# Skaarhoj_BI8-1x8v1_1.net
KiCad netlist of a schematic drawn in EAGLE
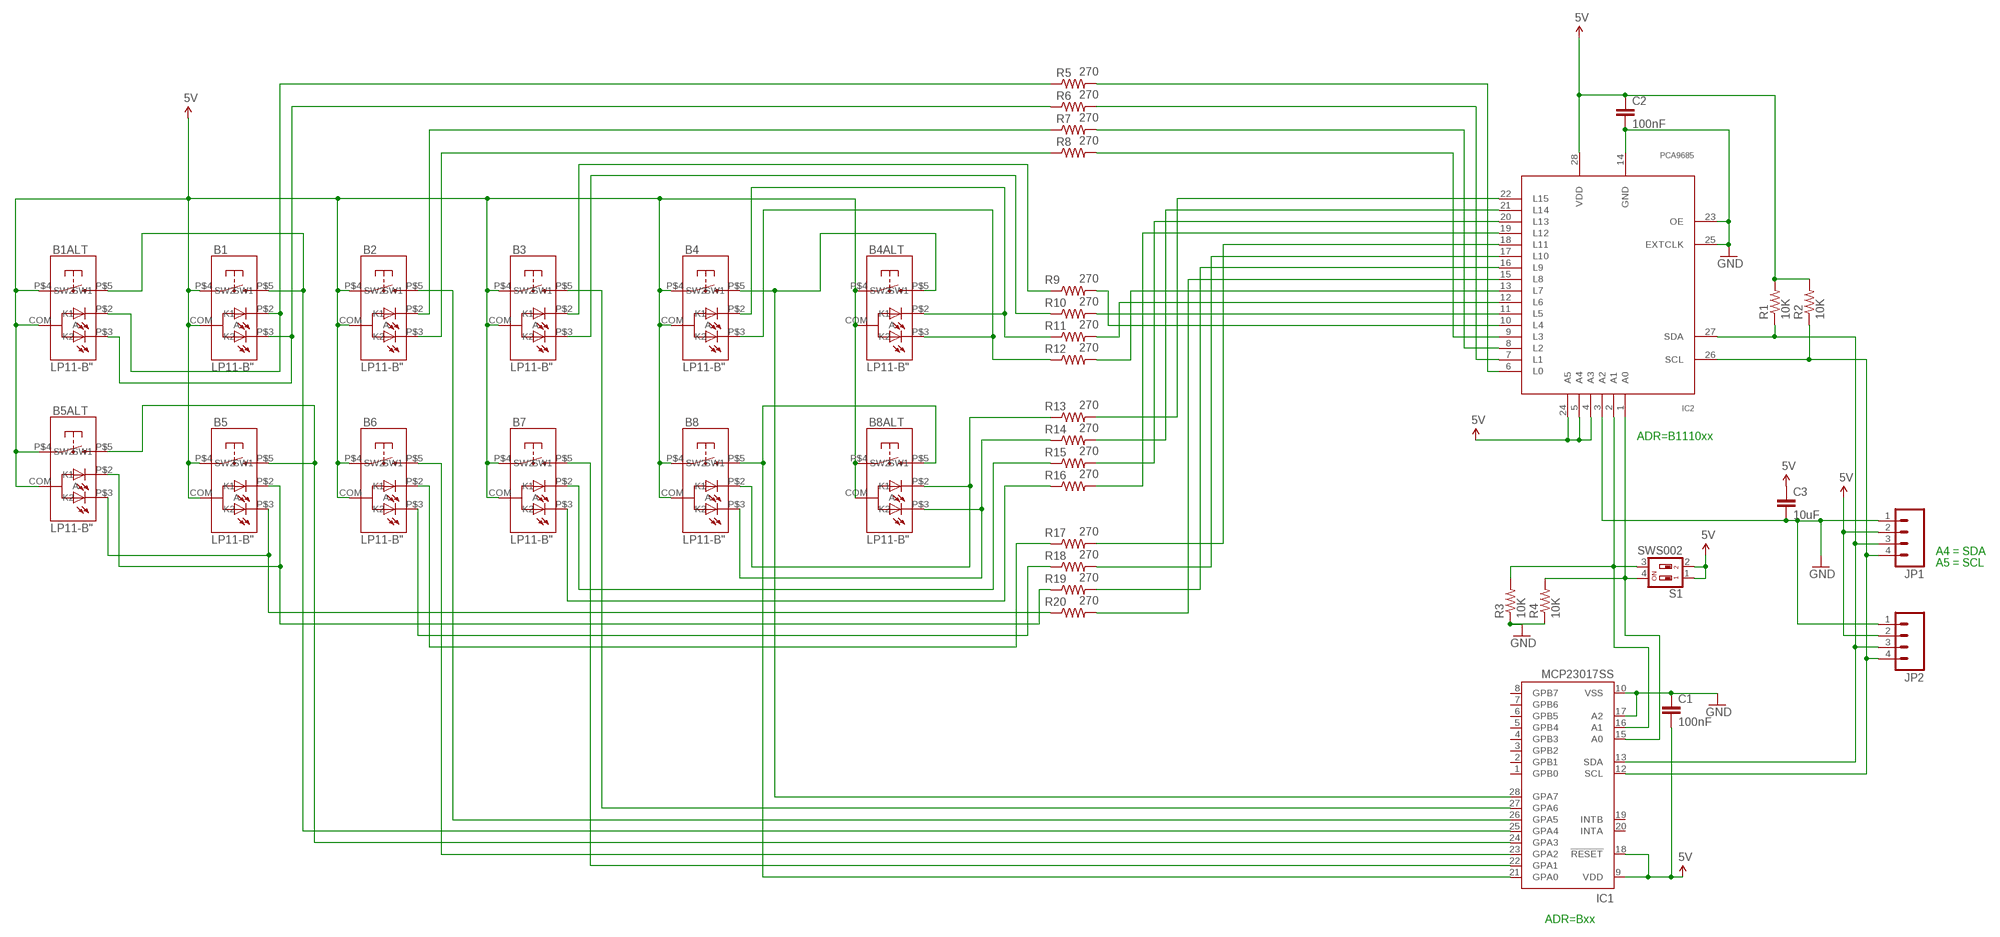
[diagram p0: schematic, sheet 1]

(export (version "E")
  (design (tool "Eeschema 10.0.6"))
  (components
    (comp (ref "B1")
      (value "LP11-B\"")
      (footprint "eagle-import:LP11")
      (libsource (lib "eagle-import") (part "LP11-B{dblquote}"))
    )
    (comp (ref "B1ALT")
      (value "LP11-B\"")
      (footprint "eagle-import:LP11")
      (libsource (lib "eagle-import") (part "LP11-B{dblquote}"))
    )
    (comp (ref "B2")
      (value "LP11-B\"")
      (footprint "eagle-import:LP11")
      (libsource (lib "eagle-import") (part "LP11-B{dblquote}"))
    )
    (comp (ref "B3")
      (value "LP11-B\"")
      (footprint "eagle-import:LP11")
      (libsource (lib "eagle-import") (part "LP11-B{dblquote}"))
    )
    (comp (ref "B4")
      (value "LP11-B\"")
      (footprint "eagle-import:LP11")
      (libsource (lib "eagle-import") (part "LP11-B{dblquote}"))
    )
    (comp (ref "B4ALT")
      (value "LP11-B\"")
      (footprint "eagle-import:LP11")
      (libsource (lib "eagle-import") (part "LP11-B{dblquote}"))
    )
    (comp (ref "B5")
      (value "LP11-B\"")
      (footprint "eagle-import:LP11")
      (libsource (lib "eagle-import") (part "LP11-B{dblquote}"))
    )
    (comp (ref "B5ALT")
      (value "LP11-B\"")
      (footprint "eagle-import:LP11")
      (libsource (lib "eagle-import") (part "LP11-B{dblquote}"))
    )
    (comp (ref "B6")
      (value "LP11-B\"")
      (footprint "eagle-import:LP11")
      (libsource (lib "eagle-import") (part "LP11-B{dblquote}"))
    )
    (comp (ref "B7")
      (value "LP11-B\"")
      (footprint "eagle-import:LP11")
      (libsource (lib "eagle-import") (part "LP11-B{dblquote}"))
    )
    (comp (ref "B8")
      (value "LP11-B\"")
      (footprint "eagle-import:LP11")
      (libsource (lib "eagle-import") (part "LP11-B{dblquote}"))
    )
    (comp (ref "B8ALT")
      (value "LP11-B\"")
      (footprint "eagle-import:LP11")
      (libsource (lib "eagle-import") (part "LP11-B{dblquote}"))
    )
    (comp (ref "C1")
      (value "100nF")
      (footprint "eagle-import:0603-CAP")
      (libsource (lib "eagle-import") (part "CAP0603-CAP"))
    )
    (comp (ref "C2")
      (value "100nF")
      (footprint "eagle-import:0603-CAP")
      (libsource (lib "eagle-import") (part "CAP0603-CAP"))
    )
    (comp (ref "C3")
      (value "10uF")
      (footprint "eagle-import:0805")
      (libsource (lib "eagle-import") (part "CAP0805"))
    )
    (comp (ref "IC1")
      (value "MCP23017SS")
      (footprint "eagle-import:SSOP28")
      (fields
        (field (name "MF") "MICROCHIP")
        (field (name "MPN") "MCP23017-E/SS")
        (field (name "MPN_1") "MCP23017-E/SS")
        (field (name "OC_FARNELL") "1467674")
        (field (name "OC_NEWARK") "31K2960")
      )
      (libsource (lib "eagle-import") (part "MCP23017SS"))
    )
    (comp (ref "IC2")
      (value "PCA9685")
      (footprint "eagle-import:TSSOP28")
      (libsource (lib "eagle-import") (part "PCA9685"))
    )
    (comp (ref "JP1")
      (value "M04PTH")
      (footprint "eagle-import:1X04")
      (libsource (lib "eagle-import") (part "M04PTH"))
    )
    (comp (ref "JP2")
      (value "M04PTH")
      (footprint "eagle-import:1X04")
      (libsource (lib "eagle-import") (part "M04PTH"))
    )
    (comp (ref "R1")
      (value "10K")
      (footprint "eagle-import:0603-RES")
      (libsource (lib "eagle-import") (part "RESISTOR0603-RES"))
    )
    (comp (ref "R2")
      (value "10K")
      (footprint "eagle-import:0603-RES")
      (libsource (lib "eagle-import") (part "RESISTOR0603-RES"))
    )
    (comp (ref "R3")
      (value "10K")
      (footprint "eagle-import:0603-RES")
      (libsource (lib "eagle-import") (part "RESISTOR0603-RES"))
    )
    (comp (ref "R4")
      (value "10K")
      (footprint "eagle-import:0603-RES")
      (libsource (lib "eagle-import") (part "RESISTOR0603-RES"))
    )
    (comp (ref "R5")
      (value "270")
      (footprint "eagle-import:0603-RES")
      (libsource (lib "eagle-import") (part "RESISTOR0603-RES"))
    )
    (comp (ref "R6")
      (value "270")
      (footprint "eagle-import:0603-RES")
      (libsource (lib "eagle-import") (part "RESISTOR0603-RES"))
    )
    (comp (ref "R7")
      (value "270")
      (footprint "eagle-import:0603-RES")
      (libsource (lib "eagle-import") (part "RESISTOR0603-RES"))
    )
    (comp (ref "R8")
      (value "270")
      (footprint "eagle-import:0603-RES")
      (libsource (lib "eagle-import") (part "RESISTOR0603-RES"))
    )
    (comp (ref "R9")
      (value "270")
      (footprint "eagle-import:0603-RES")
      (libsource (lib "eagle-import") (part "RESISTOR0603-RES"))
    )
    (comp (ref "R10")
      (value "270")
      (footprint "eagle-import:0603-RES")
      (libsource (lib "eagle-import") (part "RESISTOR0603-RES"))
    )
    (comp (ref "R11")
      (value "270")
      (footprint "eagle-import:0603-RES")
      (libsource (lib "eagle-import") (part "RESISTOR0603-RES"))
    )
    (comp (ref "R12")
      (value "270")
      (footprint "eagle-import:0603-RES")
      (libsource (lib "eagle-import") (part "RESISTOR0603-RES"))
    )
    (comp (ref "R13")
      (value "270")
      (footprint "eagle-import:0603-RES")
      (libsource (lib "eagle-import") (part "RESISTOR0603-RES"))
    )
    (comp (ref "R14")
      (value "270")
      (footprint "eagle-import:0603-RES")
      (libsource (lib "eagle-import") (part "RESISTOR0603-RES"))
    )
    (comp (ref "R15")
      (value "270")
      (footprint "eagle-import:0603-RES")
      (libsource (lib "eagle-import") (part "RESISTOR0603-RES"))
    )
    (comp (ref "R16")
      (value "270")
      (footprint "eagle-import:0603-RES")
      (libsource (lib "eagle-import") (part "RESISTOR0603-RES"))
    )
    (comp (ref "R17")
      (value "270")
      (footprint "eagle-import:0603-RES")
      (libsource (lib "eagle-import") (part "RESISTOR0603-RES"))
    )
    (comp (ref "R18")
      (value "270")
      (footprint "eagle-import:0603-RES")
      (libsource (lib "eagle-import") (part "RESISTOR0603-RES"))
    )
    (comp (ref "R19")
      (value "270")
      (footprint "eagle-import:0603-RES")
      (libsource (lib "eagle-import") (part "RESISTOR0603-RES"))
    )
    (comp (ref "R20")
      (value "270")
      (footprint "eagle-import:0603-RES")
      (libsource (lib "eagle-import") (part "RESISTOR0603-RES"))
    )
    (comp (ref "S1")
      (value "SWS002")
      (footprint "eagle-import:SMS-002")
      (libsource (lib "eagle-import") (part "SWS002"))
    )
  )
  (nets
    (net (code "1") (name "5V") (class "Default")
      (node (ref "B1") (pin "COM") (pinfunction "A_COM") (pintype "bidirectional"))
      (node (ref "B1") (pin "P$4") (pinfunction "SW1_P$4") (pintype "bidirectional"))
      (node (ref "B1ALT") (pin "COM") (pinfunction "A_COM") (pintype "bidirectional"))
      (node (ref "B1ALT") (pin "P$4") (pinfunction "SW1_P$4") (pintype "bidirectional"))
      (node (ref "B2") (pin "COM") (pinfunction "A_COM") (pintype "bidirectional"))
      (node (ref "B2") (pin "P$4") (pinfunction "SW1_P$4") (pintype "bidirectional"))
      (node (ref "B3") (pin "COM") (pinfunction "A_COM") (pintype "bidirectional"))
      (node (ref "B3") (pin "P$4") (pinfunction "SW1_P$4") (pintype "bidirectional"))
      (node (ref "B4") (pin "COM") (pinfunction "A_COM") (pintype "bidirectional"))
      (node (ref "B4") (pin "P$4") (pinfunction "SW1_P$4") (pintype "bidirectional"))
      (node (ref "B4ALT") (pin "COM") (pinfunction "A_COM") (pintype "bidirectional"))
      (node (ref "B4ALT") (pin "P$4") (pinfunction "SW1_P$4") (pintype "bidirectional"))
      (node (ref "B5") (pin "COM") (pinfunction "A_COM") (pintype "bidirectional"))
      (node (ref "B5") (pin "P$4") (pinfunction "SW1_P$4") (pintype "bidirectional"))
      (node (ref "B5ALT") (pin "COM") (pinfunction "A_COM") (pintype "bidirectional"))
      (node (ref "B5ALT") (pin "P$4") (pinfunction "SW1_P$4") (pintype "bidirectional"))
      (node (ref "B6") (pin "COM") (pinfunction "A_COM") (pintype "bidirectional"))
      (node (ref "B6") (pin "P$4") (pinfunction "SW1_P$4") (pintype "bidirectional"))
      (node (ref "B7") (pin "COM") (pinfunction "A_COM") (pintype "bidirectional"))
      (node (ref "B7") (pin "P$4") (pinfunction "SW1_P$4") (pintype "bidirectional"))
      (node (ref "B8") (pin "COM") (pinfunction "A_COM") (pintype "bidirectional"))
      (node (ref "B8") (pin "P$4") (pinfunction "SW1_P$4") (pintype "bidirectional"))
      (node (ref "B8ALT") (pin "COM") (pinfunction "A_COM") (pintype "bidirectional"))
      (node (ref "B8ALT") (pin "P$4") (pinfunction "SW1_P$4") (pintype "bidirectional"))
      (node (ref "C1") (pin "2") (pinfunction "2_2") (pintype "passive"))
      (node (ref "C2") (pin "1") (pinfunction "1_1") (pintype "passive"))
      (node (ref "C3") (pin "1") (pinfunction "1_1") (pintype "passive"))
      (node (ref "IC1") (pin "18") (pinfunction "~{RESET}_18") (pintype "input"))
      (node (ref "IC1") (pin "9") (pinfunction "VDD_9") (pintype "power_in"))
      (node (ref "IC2") (pin "24") (pinfunction "A5_24") (pintype "input"))
      (node (ref "IC2") (pin "28") (pinfunction "VDD_28") (pintype "power_in"))
      (node (ref "IC2") (pin "4") (pinfunction "A3_4") (pintype "input"))
      (node (ref "IC2") (pin "5") (pinfunction "A4_5") (pintype "input"))
      (node (ref "JP1") (pin "2") (pinfunction "2_2") (pintype "passive"))
      (node (ref "JP2") (pin "2") (pinfunction "2_2") (pintype "passive"))
      (node (ref "R1") (pin "2") (pinfunction "2_2") (pintype "passive"))
      (node (ref "R2") (pin "2") (pinfunction "2_2") (pintype "passive"))
      (node (ref "S1") (pin "1") (pinfunction "1_1") (pintype "passive"))
      (node (ref "S1") (pin "2") (pinfunction "2_2") (pintype "passive"))
    )
    (net (code "2") (name "GND") (class "Default")
      (node (ref "C1") (pin "1") (pinfunction "1_1") (pintype "passive"))
      (node (ref "C2") (pin "2") (pinfunction "2_2") (pintype "passive"))
      (node (ref "C3") (pin "2") (pinfunction "2_2") (pintype "passive"))
      (node (ref "IC1") (pin "10") (pinfunction "VSS_10") (pintype "power_in"))
      (node (ref "IC1") (pin "17") (pinfunction "A2_17") (pintype "input"))
      (node (ref "IC2") (pin "14") (pinfunction "GND_14") (pintype "power_in"))
      (node (ref "IC2") (pin "23") (pinfunction "OE_23") (pintype "input"))
      (node (ref "IC2") (pin "25") (pinfunction "EXTCLK_25") (pintype "input"))
      (node (ref "IC2") (pin "3") (pinfunction "A2_3") (pintype "input"))
      (node (ref "JP1") (pin "1") (pinfunction "1_1") (pintype "passive"))
      (node (ref "JP2") (pin "1") (pinfunction "1_1") (pintype "passive"))
      (node (ref "R3") (pin "1") (pinfunction "1_1") (pintype "passive"))
      (node (ref "R4") (pin "1") (pinfunction "1_1") (pintype "passive"))
    )
    (net (code "3") (name "Net-(B1-K1)") (class "Default")
      (node (ref "B1") (pin "P$2") (pinfunction "K1_P$2") (pintype "bidirectional"))
      (node (ref "B1ALT") (pin "P$2") (pinfunction "K1_P$2") (pintype "bidirectional"))
      (node (ref "R5") (pin "1") (pinfunction "1_1") (pintype "passive"))
    )
    (net (code "4") (name "Net-(B1-K2)") (class "Default")
      (node (ref "B1") (pin "P$3") (pinfunction "K2_P$3") (pintype "bidirectional"))
      (node (ref "B1ALT") (pin "P$3") (pinfunction "K2_P$3") (pintype "bidirectional"))
      (node (ref "R6") (pin "1") (pinfunction "1_1") (pintype "passive"))
    )
    (net (code "5") (name "Net-(B1-SW2)") (class "Default")
      (node (ref "B1") (pin "P$5") (pinfunction "SW2_P$5") (pintype "bidirectional"))
      (node (ref "B1ALT") (pin "P$5") (pinfunction "SW2_P$5") (pintype "bidirectional"))
      (node (ref "IC1") (pin "25") (pinfunction "GPA4_25") (pintype "bidirectional"))
    )
    (net (code "6") (name "Net-(B2-K1)") (class "Default")
      (node (ref "B2") (pin "P$2") (pinfunction "K1_P$2") (pintype "bidirectional"))
      (node (ref "R7") (pin "1") (pinfunction "1_1") (pintype "passive"))
    )
    (net (code "7") (name "Net-(B2-K2)") (class "Default")
      (node (ref "B2") (pin "P$3") (pinfunction "K2_P$3") (pintype "bidirectional"))
      (node (ref "R8") (pin "1") (pinfunction "1_1") (pintype "passive"))
    )
    (net (code "8") (name "Net-(B2-SW2)") (class "Default")
      (node (ref "B2") (pin "P$5") (pinfunction "SW2_P$5") (pintype "bidirectional"))
      (node (ref "IC1") (pin "26") (pinfunction "GPA5_26") (pintype "bidirectional"))
    )
    (net (code "9") (name "Net-(B3-K1)") (class "Default")
      (node (ref "B3") (pin "P$2") (pinfunction "K1_P$2") (pintype "bidirectional"))
      (node (ref "R9") (pin "1") (pinfunction "1_1") (pintype "passive"))
    )
    (net (code "10") (name "Net-(B3-K2)") (class "Default")
      (node (ref "B3") (pin "P$3") (pinfunction "K2_P$3") (pintype "bidirectional"))
      (node (ref "R10") (pin "1") (pinfunction "1_1") (pintype "passive"))
    )
    (net (code "11") (name "Net-(B3-SW2)") (class "Default")
      (node (ref "B3") (pin "P$5") (pinfunction "SW2_P$5") (pintype "bidirectional"))
      (node (ref "IC1") (pin "27") (pinfunction "GPA6_27") (pintype "bidirectional"))
    )
    (net (code "12") (name "Net-(B4-K1)") (class "Default")
      (node (ref "B4") (pin "P$2") (pinfunction "K1_P$2") (pintype "bidirectional"))
      (node (ref "B4ALT") (pin "P$2") (pinfunction "K1_P$2") (pintype "bidirectional"))
      (node (ref "R11") (pin "1") (pinfunction "1_1") (pintype "passive"))
    )
    (net (code "13") (name "Net-(B4-K2)") (class "Default")
      (node (ref "B4") (pin "P$3") (pinfunction "K2_P$3") (pintype "bidirectional"))
      (node (ref "B4ALT") (pin "P$3") (pinfunction "K2_P$3") (pintype "bidirectional"))
      (node (ref "R12") (pin "1") (pinfunction "1_1") (pintype "passive"))
    )
    (net (code "14") (name "Net-(B4-SW2)") (class "Default")
      (node (ref "B4") (pin "P$5") (pinfunction "SW2_P$5") (pintype "bidirectional"))
      (node (ref "B4ALT") (pin "P$5") (pinfunction "SW2_P$5") (pintype "bidirectional"))
      (node (ref "IC1") (pin "28") (pinfunction "GPA7_28") (pintype "bidirectional"))
    )
    (net (code "15") (name "Net-(B5-K1)") (class "Default")
      (node (ref "B5") (pin "P$2") (pinfunction "K1_P$2") (pintype "bidirectional"))
      (node (ref "B5ALT") (pin "P$2") (pinfunction "K1_P$2") (pintype "bidirectional"))
      (node (ref "R19") (pin "1") (pinfunction "1_1") (pintype "passive"))
    )
    (net (code "16") (name "Net-(B5-K2)") (class "Default")
      (node (ref "B5") (pin "P$3") (pinfunction "K2_P$3") (pintype "bidirectional"))
      (node (ref "B5ALT") (pin "P$3") (pinfunction "K2_P$3") (pintype "bidirectional"))
      (node (ref "R20") (pin "1") (pinfunction "1_1") (pintype "passive"))
    )
    (net (code "17") (name "Net-(B5-SW2)") (class "Default")
      (node (ref "B5") (pin "P$5") (pinfunction "SW2_P$5") (pintype "bidirectional"))
      (node (ref "B5ALT") (pin "P$5") (pinfunction "SW2_P$5") (pintype "bidirectional"))
      (node (ref "IC1") (pin "24") (pinfunction "GPA3_24") (pintype "bidirectional"))
    )
    (net (code "18") (name "Net-(B6-K1)") (class "Default")
      (node (ref "B6") (pin "P$2") (pinfunction "K1_P$2") (pintype "bidirectional"))
      (node (ref "R17") (pin "1") (pinfunction "1_1") (pintype "passive"))
    )
    (net (code "19") (name "Net-(B6-K2)") (class "Default")
      (node (ref "B6") (pin "P$3") (pinfunction "K2_P$3") (pintype "bidirectional"))
      (node (ref "R18") (pin "1") (pinfunction "1_1") (pintype "passive"))
    )
    (net (code "20") (name "Net-(B6-SW2)") (class "Default")
      (node (ref "B6") (pin "P$5") (pinfunction "SW2_P$5") (pintype "bidirectional"))
      (node (ref "IC1") (pin "23") (pinfunction "GPA2_23") (pintype "bidirectional"))
    )
    (net (code "21") (name "Net-(B7-K1)") (class "Default")
      (node (ref "B7") (pin "P$2") (pinfunction "K1_P$2") (pintype "bidirectional"))
      (node (ref "R15") (pin "1") (pinfunction "1_1") (pintype "passive"))
    )
    (net (code "22") (name "Net-(B7-K2)") (class "Default")
      (node (ref "B7") (pin "P$3") (pinfunction "K2_P$3") (pintype "bidirectional"))
      (node (ref "R16") (pin "1") (pinfunction "1_1") (pintype "passive"))
    )
    (net (code "23") (name "Net-(B7-SW2)") (class "Default")
      (node (ref "B7") (pin "P$5") (pinfunction "SW2_P$5") (pintype "bidirectional"))
      (node (ref "IC1") (pin "22") (pinfunction "GPA1_22") (pintype "bidirectional"))
    )
    (net (code "24") (name "Net-(B8-K1)") (class "Default")
      (node (ref "B8") (pin "P$2") (pinfunction "K1_P$2") (pintype "bidirectional"))
      (node (ref "B8ALT") (pin "P$2") (pinfunction "K1_P$2") (pintype "bidirectional"))
      (node (ref "R13") (pin "1") (pinfunction "1_1") (pintype "passive"))
    )
    (net (code "25") (name "Net-(B8-K2)") (class "Default")
      (node (ref "B8") (pin "P$3") (pinfunction "K2_P$3") (pintype "bidirectional"))
      (node (ref "B8ALT") (pin "P$3") (pinfunction "K2_P$3") (pintype "bidirectional"))
      (node (ref "R14") (pin "1") (pinfunction "1_1") (pintype "passive"))
    )
    (net (code "26") (name "Net-(B8-SW2)") (class "Default")
      (node (ref "B8") (pin "P$5") (pinfunction "SW2_P$5") (pintype "bidirectional"))
      (node (ref "B8ALT") (pin "P$5") (pinfunction "SW2_P$5") (pintype "bidirectional"))
      (node (ref "IC1") (pin "21") (pinfunction "GPA0_21") (pintype "bidirectional"))
    )
    (net (code "27") (name "Net-(IC1-A0)") (class "Default")
      (node (ref "IC1") (pin "15") (pinfunction "A0_15") (pintype "input"))
      (node (ref "IC2") (pin "1") (pinfunction "A0_1") (pintype "input"))
      (node (ref "R4") (pin "2") (pinfunction "2_2") (pintype "passive"))
      (node (ref "S1") (pin "4") (pinfunction "4_4") (pintype "passive"))
    )
    (net (code "28") (name "Net-(IC1-A1)") (class "Default")
      (node (ref "IC1") (pin "16") (pinfunction "A1_16") (pintype "input"))
      (node (ref "IC2") (pin "2") (pinfunction "A1_2") (pintype "input"))
      (node (ref "R3") (pin "2") (pinfunction "2_2") (pintype "passive"))
      (node (ref "S1") (pin "3") (pinfunction "3_3") (pintype "passive"))
    )
    (net (code "29") (name "Net-(IC1-SCL)") (class "Default")
      (node (ref "IC1") (pin "12") (pinfunction "SCL_12") (pintype "input"))
      (node (ref "IC2") (pin "26") (pinfunction "SCL_26") (pintype "input"))
      (node (ref "JP1") (pin "4") (pinfunction "4_4") (pintype "passive"))
      (node (ref "JP2") (pin "4") (pinfunction "4_4") (pintype "passive"))
      (node (ref "R2") (pin "1") (pinfunction "1_1") (pintype "passive"))
    )
    (net (code "30") (name "Net-(IC1-SDA)") (class "Default")
      (node (ref "IC1") (pin "13") (pinfunction "SDA_13") (pintype "bidirectional"))
      (node (ref "IC2") (pin "27") (pinfunction "SDA_27") (pintype "input"))
      (node (ref "JP1") (pin "3") (pinfunction "3_3") (pintype "passive"))
      (node (ref "JP2") (pin "3") (pinfunction "3_3") (pintype "passive"))
      (node (ref "R1") (pin "1") (pinfunction "1_1") (pintype "passive"))
    )
    (net (code "31") (name "Net-(IC2-L0)") (class "Default")
      (node (ref "IC2") (pin "6") (pinfunction "L0_6") (pintype "output"))
      (node (ref "R5") (pin "2") (pinfunction "2_2") (pintype "passive"))
    )
    (net (code "32") (name "Net-(IC2-L1)") (class "Default")
      (node (ref "IC2") (pin "7") (pinfunction "L1_7") (pintype "output"))
      (node (ref "R6") (pin "2") (pinfunction "2_2") (pintype "passive"))
    )
    (net (code "33") (name "Net-(IC2-L2)") (class "Default")
      (node (ref "IC2") (pin "8") (pinfunction "L2_8") (pintype "output"))
      (node (ref "R7") (pin "2") (pinfunction "2_2") (pintype "passive"))
    )
    (net (code "34") (name "Net-(IC2-L3)") (class "Default")
      (node (ref "IC2") (pin "9") (pinfunction "L3_9") (pintype "output"))
      (node (ref "R8") (pin "2") (pinfunction "2_2") (pintype "passive"))
    )
    (net (code "35") (name "Net-(IC2-L4)") (class "Default")
      (node (ref "IC2") (pin "10") (pinfunction "L4_10") (pintype "output"))
      (node (ref "R9") (pin "2") (pinfunction "2_2") (pintype "passive"))
    )
    (net (code "36") (name "Net-(IC2-L5)") (class "Default")
      (node (ref "IC2") (pin "11") (pinfunction "L5_11") (pintype "output"))
      (node (ref "R10") (pin "2") (pinfunction "2_2") (pintype "passive"))
    )
    (net (code "37") (name "Net-(IC2-L6)") (class "Default")
      (node (ref "IC2") (pin "12") (pinfunction "L6_12") (pintype "output"))
      (node (ref "R11") (pin "2") (pinfunction "2_2") (pintype "passive"))
    )
    (net (code "38") (name "Net-(IC2-L7)") (class "Default")
      (node (ref "IC2") (pin "13") (pinfunction "L7_13") (pintype "output"))
      (node (ref "R12") (pin "2") (pinfunction "2_2") (pintype "passive"))
    )
    (net (code "39") (name "Net-(IC2-L8)") (class "Default")
      (node (ref "IC2") (pin "15") (pinfunction "L8_15") (pintype "output"))
      (node (ref "R20") (pin "2") (pinfunction "2_2") (pintype "passive"))
    )
    (net (code "40") (name "Net-(IC2-L9)") (class "Default")
      (node (ref "IC2") (pin "16") (pinfunction "L9_16") (pintype "output"))
      (node (ref "R19") (pin "2") (pinfunction "2_2") (pintype "passive"))
    )
    (net (code "41") (name "Net-(IC2-L10)") (class "Default")
      (node (ref "IC2") (pin "17") (pinfunction "L10_17") (pintype "output"))
      (node (ref "R18") (pin "2") (pinfunction "2_2") (pintype "passive"))
    )
    (net (code "42") (name "Net-(IC2-L11)") (class "Default")
      (node (ref "IC2") (pin "18") (pinfunction "L11_18") (pintype "output"))
      (node (ref "R17") (pin "2") (pinfunction "2_2") (pintype "passive"))
    )
    (net (code "43") (name "Net-(IC2-L12)") (class "Default")
      (node (ref "IC2") (pin "19") (pinfunction "L12_19") (pintype "output"))
      (node (ref "R16") (pin "2") (pinfunction "2_2") (pintype "passive"))
    )
    (net (code "44") (name "Net-(IC2-L13)") (class "Default")
      (node (ref "IC2") (pin "20") (pinfunction "L13_20") (pintype "output"))
      (node (ref "R15") (pin "2") (pinfunction "2_2") (pintype "passive"))
    )
    (net (code "45") (name "Net-(IC2-L14)") (class "Default")
      (node (ref "IC2") (pin "21") (pinfunction "L14_21") (pintype "output"))
      (node (ref "R14") (pin "2") (pinfunction "2_2") (pintype "passive"))
    )
    (net (code "46") (name "Net-(IC2-L15)") (class "Default")
      (node (ref "IC2") (pin "22") (pinfunction "L15_22") (pintype "output"))
      (node (ref "R13") (pin "2") (pinfunction "2_2") (pintype "passive"))
    )
    (net (code "47") (name "unconnected-(IC1-GPB0-Pad1)") (class "Default")
      (node (ref "IC1") (pin "1") (pinfunction "GPB0_1") (pintype "bidirectional"))
    )
    (net (code "48") (name "unconnected-(IC1-GPB1-Pad2)") (class "Default")
      (node (ref "IC1") (pin "2") (pinfunction "GPB1_2") (pintype "bidirectional"))
    )
    (net (code "49") (name "unconnected-(IC1-GPB2-Pad3)") (class "Default")
      (node (ref "IC1") (pin "3") (pinfunction "GPB2_3") (pintype "bidirectional"))
    )
    (net (code "50") (name "unconnected-(IC1-GPB3-Pad4)") (class "Default")
      (node (ref "IC1") (pin "4") (pinfunction "GPB3_4") (pintype "bidirectional"))
    )
    (net (code "51") (name "unconnected-(IC1-GPB4-Pad5)") (class "Default")
      (node (ref "IC1") (pin "5") (pinfunction "GPB4_5") (pintype "bidirectional"))
    )
    (net (code "52") (name "unconnected-(IC1-GPB5-Pad6)") (class "Default")
      (node (ref "IC1") (pin "6") (pinfunction "GPB5_6") (pintype "bidirectional"))
    )
    (net (code "53") (name "unconnected-(IC1-GPB6-Pad7)") (class "Default")
      (node (ref "IC1") (pin "7") (pinfunction "GPB6_7") (pintype "bidirectional"))
    )
    (net (code "54") (name "unconnected-(IC1-GPB7-Pad8)") (class "Default")
      (node (ref "IC1") (pin "8") (pinfunction "GPB7_8") (pintype "bidirectional"))
    )
    (net (code "55") (name "unconnected-(IC1-INTA-Pad20)") (class "Default")
      (node (ref "IC1") (pin "20") (pinfunction "INTA_20") (pintype "output"))
    )
    (net (code "56") (name "unconnected-(IC1-INTB-Pad19)") (class "Default")
      (node (ref "IC1") (pin "19") (pinfunction "INTB_19") (pintype "output"))
    )
  )
)
